# simplefoc.net
KiCad netlist of a schematic drawn in Altium Designer
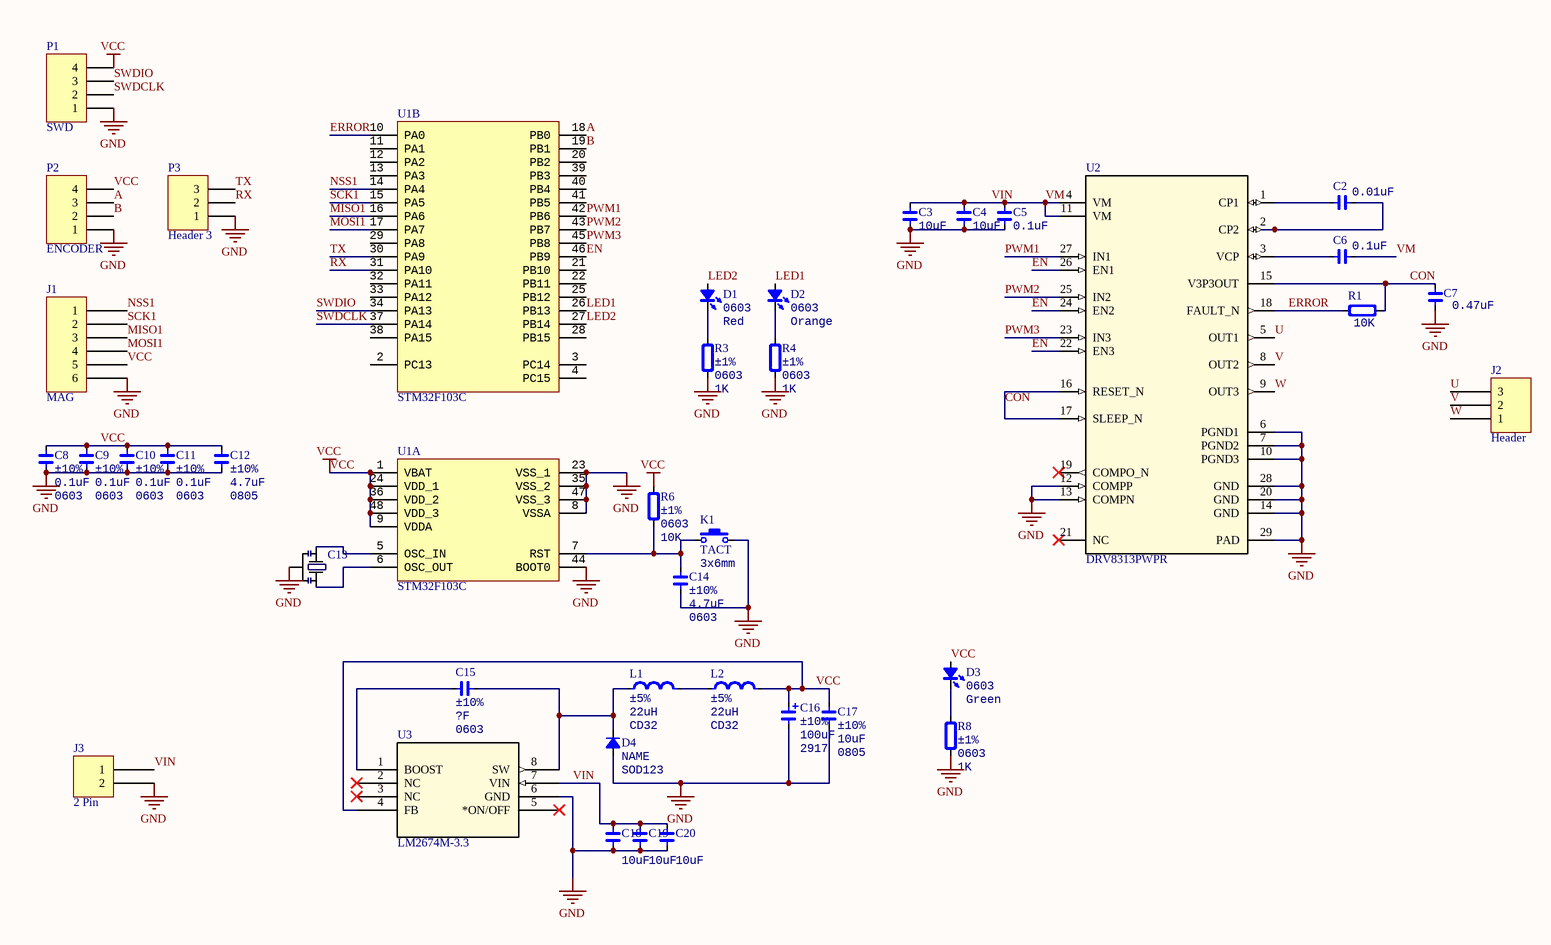
[diagram p0: simplefoc.SchDoc]

(export (version "E")
  (design (tool "Eeschema 10.0.6"))
  (components
    (comp (ref "C2")
      (value "0.01uF")
      (footprint "PCB_PassiveCap:CAP_0603")
      (description "Capacitor")
      (fields (field (name "Comment") "C0603"))
      (libsource (lib "") (part "Cap_0603_1"))
    )
    (comp (ref "C3")
      (value "10uF")
      (footprint "PCB_PassiveCap:CAP_0805")
      (description "Capacitor")
      (fields (field (name "Comment") "C0805"))
      (libsource (lib "SCH_Passive") (part "Cap_0805"))
    )
    (comp (ref "C4")
      (value "10uF")
      (footprint "PCB_PassiveCap:CAP_0805")
      (description "Capacitor")
      (fields (field (name "Comment") "C0805"))
      (libsource (lib "SCH_Passive") (part "Cap_0805"))
    )
    (comp (ref "C5")
      (value "0.1uF")
      (footprint "PCB_PassiveCap:CAP_0603")
      (description "Capacitor")
      (fields (field (name "Comment") "C0603"))
      (libsource (lib "SCH_Passive") (part "Cap_0603"))
    )
    (comp (ref "C6")
      (value "0.1uF")
      (footprint "PCB_PassiveCap:CAP_0603")
      (description "Capacitor")
      (fields (field (name "Comment") "C0603"))
      (libsource (lib "") (part "Cap_0603_1"))
    )
    (comp (ref "C7")
      (value "0.47uF")
      (footprint "PCB_PassiveCap:CAP_0603")
      (description "Capacitor")
      (fields (field (name "Comment") "C0603"))
      (libsource (lib "SCH_Passive") (part "Cap_0603"))
    )
    (comp (ref "C8")
      (value "0.1uF")
      (footprint "PCB_PassiveCap:CAP_0603")
      (description "Capacitor")
      (fields (field (name "NOTE") "±10%") (field (name "TYPE") "0603") (field (name "Comment") "C0603"))
      (libsource (lib "SCH_Passive") (part "Cap_0603"))
    )
    (comp (ref "C9")
      (value "0.1uF")
      (footprint "PCB_PassiveCap:CAP_0603")
      (description "Capacitor")
      (fields (field (name "NOTE") "±10%") (field (name "TYPE") "0603") (field (name "Comment") "C0603"))
      (libsource (lib "SCH_Passive") (part "Cap_0603"))
    )
    (comp (ref "C10")
      (value "0.1uF")
      (footprint "PCB_PassiveCap:CAP_0603")
      (description "Capacitor")
      (fields (field (name "NOTE") "±10%") (field (name "TYPE") "0603") (field (name "Comment") "C0603"))
      (libsource (lib "SCH_Passive") (part "Cap_0603"))
    )
    (comp (ref "C11")
      (value "0.1uF")
      (footprint "PCB_PassiveCap:CAP_0603")
      (description "Capacitor")
      (fields (field (name "NOTE") "±10%") (field (name "TYPE") "0603") (field (name "Comment") "C0603"))
      (libsource (lib "SCH_Passive") (part "Cap_0603"))
    )
    (comp (ref "C12")
      (value "4.7uF")
      (footprint "PCB_PassiveCap:CAP_0805")
      (description "Capacitor")
      (fields (field (name "NOTE") "±10%") (field (name "TYPE") "0805") (field (name "Comment") "C0805"))
      (libsource (lib "SCH_Passive") (part "Cap_0805"))
    )
    (comp (ref "C13")
      (value "CSTCE8M00G52-R0")
      (footprint "CSTCE_MUR")
      (description "No Description Available")
      (fields (field (name "COPYRIGHT") "Copyright (C) 2018 Accelerated Designs. All rights reserved"))
      (libsource (lib "Schlib1") (part "CSTCE8M00G52-R0"))
    )
    (comp (ref "C14")
      (value "4.7uF")
      (footprint "PCB_PassiveCap:CAP_0603")
      (description "Capacitor")
      (fields (field (name "NOTE") "±10%") (field (name "TYPE") "0603") (field (name "Comment") "C0603"))
      (libsource (lib "SCH_Passive") (part "Cap_0603"))
    )
    (comp (ref "C15")
      (value "?F")
      (footprint "PCB_PassiveCap:CAP_0603")
      (description "Capacitor")
      (fields (field (name "NOTE") "±10%") (field (name "TYPE") "0603") (field (name "Comment") "C0603"))
      (libsource (lib "") (part "Cap_0603_1"))
    )
    (comp (ref "C16")
      (value "100uF")
      (footprint "PCB_PassiveCap:CAP_TAN_D2917")
      (description "Capacitor Tantalum")
      (fields (field (name "NOTE") "±10%") (field (name "TYPE") "2917") (field (name "Comment") "C2917"))
      (libsource (lib "SCH_Passive") (part "Cap_Tan_2917"))
    )
    (comp (ref "C17")
      (value "10uF")
      (footprint "PCB_PassiveCap:CAP_0805")
      (description "Capacitor")
      (fields (field (name "NOTE") "±10%") (field (name "TYPE") "0805") (field (name "Comment") "C0805"))
      (libsource (lib "SCH_Passive") (part "Cap_0805"))
    )
    (comp (ref "C18")
      (value "10uF")
      (footprint "PCB_PassiveCap:CAP_0805")
      (description "Capacitor")
      (fields (field (name "Comment") "C0805"))
      (libsource (lib "SCH_Passive") (part "Cap_0805"))
    )
    (comp (ref "C19")
      (value "10uF")
      (footprint "PCB_PassiveCap:CAP_0805")
      (description "Capacitor")
      (fields (field (name "Comment") "C0805"))
      (libsource (lib "SCH_Passive") (part "Cap_0805"))
    )
    (comp (ref "C20")
      (value "10uF")
      (footprint "PCB_PassiveCap:CAP_0805")
      (description "Capacitor")
      (fields (field (name "Comment") "C0805"))
      (libsource (lib "SCH_Passive") (part "Cap_0805"))
    )
    (comp (ref "D1")
      (value "Red")
      (footprint "PCB_ActiveLED:LED_0603_RED")
      (description "LED")
      (fields (field (name "TYPE") "0603") (field (name "Comment") "D0603"))
      (libsource (lib "SCH_Active") (part "LED_0603"))
    )
    (comp (ref "D2")
      (value "Orange")
      (footprint "PCB_ActiveLED:LED_0603_RED")
      (description "LED")
      (fields (field (name "TYPE") "0603") (field (name "Comment") "D0603"))
      (libsource (lib "SCH_Active") (part "LED_0603"))
    )
    (comp (ref "D3")
      (value "Green")
      (footprint "PCB_ActiveLED:LED_0603_RED")
      (description "LED")
      (fields (field (name "TYPE") "0603") (field (name "Comment") "D0603"))
      (libsource (lib "SCH_Active") (part "LED_0603"))
    )
    (comp (ref "D4")
      (value "NAME")
      (footprint "PCB_ActiveDIO:SOD-123")
      (description "Diode")
      (fields (field (name "TYPE") "SOD123"))
      (libsource (lib "SCH_Active") (part "Diode_SOD123"))
    )
    (comp (ref "J1")
      (value "MAG")
      (footprint "JST BM06B-GHS-TBT")
      (libsource (lib "SCH - CONNECTORS - 6 PIN") (part "6 Pin"))
    )
    (comp (ref "J2")
      (value "Header")
      (footprint "Motor_WIRE_3")
      (libsource (lib "SCH - CONNECTORS - 3 PIN") (part "3 Pin"))
    )
    (comp (ref "J3")
      (value "2 Pin")
      (footprint "MOLEX KK 0022272021")
      (libsource (lib "SCH - CONNECTORS - 2 PIN") (part "2 Pin"))
    )
    (comp (ref "K1")
      (value "TACT")
      (footprint "PCB_Switch:ButtonTACT_3x6x2.5_180")
      (description "Button")
      (fields (field (name "ALTIUM_VALUE") "3x6mm"))
      (libsource (lib "SCH_Switch") (part "ButtonTACT_180_3x6x2.5"))
    )
    (comp (ref "L1")
      (value "22uH")
      (footprint "PCB_PassiveInd:IND_CD32")
      (description "Power Inductor")
      (fields (field (name "NOTE") "±5%") (field (name "TYPE") "CD32") (field (name "Comment") "CD32"))
      (libsource (lib "SCH_Passive") (part "Ind_CD32"))
    )
    (comp (ref "L2")
      (value "22uH")
      (footprint "PCB_PassiveInd:IND_CD32")
      (description "Power Inductor")
      (fields (field (name "NOTE") "±5%") (field (name "TYPE") "CD32") (field (name "Comment") "CD32"))
      (libsource (lib "SCH_Passive") (part "Ind_CD32"))
    )
    (comp (ref "P1")
      (value "SWD")
      (footprint "HDR1X4")
      (description "Header, 4-Pin")
      (fields (field (name "PUBLISHER") "Altium Limited"))
      (libsource (lib "Miscellaneous Connectors") (part "Header 4"))
    )
    (comp (ref "P2")
      (value "ENCODER")
      (footprint "HDR1X4")
      (description "Header, 4-Pin")
      (fields (field (name "PUBLISHER") "Altium Limited"))
      (libsource (lib "Miscellaneous Connectors") (part "Header 4"))
    )
    (comp (ref "P3")
      (value "Header 3")
      (footprint "HDR1X3")
      (description "Header, 3-Pin")
      (fields (field (name "PUBLISHER") "Altium Limited"))
      (libsource (lib "Miscellaneous Connectors") (part "Header 3"))
    )
    (comp (ref "R1")
      (value "10K")
      (footprint "PCB_PassiveRes:RES_0603")
      (description "Resistor")
      (fields (field (name "Comment") "R0603"))
      (libsource (lib "SCH_Passive") (part "Res_0603"))
    )
    (comp (ref "R3")
      (value "1K")
      (footprint "PCB_PassiveRes:RES_0603")
      (description "Resistor")
      (fields (field (name "NOTE") "±1%") (field (name "TYPE") "0603") (field (name "Comment") "R0603"))
      (libsource (lib "SCH_Passive") (part "Res_0603"))
    )
    (comp (ref "R4")
      (value "1K")
      (footprint "PCB_PassiveRes:RES_0603")
      (description "Resistor")
      (fields (field (name "NOTE") "±1%") (field (name "TYPE") "0603") (field (name "Comment") "R0603"))
      (libsource (lib "SCH_Passive") (part "Res_0603"))
    )
    (comp (ref "R6")
      (value "10K")
      (footprint "PCB_PassiveRes:RES_0603")
      (description "Resistor")
      (fields (field (name "NOTE") "±1%") (field (name "TYPE") "0603") (field (name "Comment") "R0603"))
      (libsource (lib "SCH_Passive") (part "Res_0603"))
    )
    (comp (ref "R8")
      (value "1K")
      (footprint "PCB_PassiveRes:RES_0603")
      (description "Resistor")
      (fields (field (name "NOTE") "±1%") (field (name "TYPE") "0603") (field (name "Comment") "R0603"))
      (libsource (lib "SCH_Passive") (part "Res_0603"))
    )
    (comp (ref "U1")
      (value "STM32F103C")
      (footprint "PCB_IntegratedCircuit:LQFP_P0.5_48")
      (description "MCU ST")
      (fields (field (name "MANUFACTURER") "STMicroelectronics"))
      (libsource (lib "SCH_Microcontroller") (part "STM32F103C"))
    )
    (comp (ref "U2")
      (value "DRV8313PWPR")
      (footprint "PWP0028F_N")
      (description "No Description Available")
      (fields
        (field (name "MANUFACTURER") "Texas Instruments")
        (field (name "COPYRIGHT") "Copyright (C) 2018 Accelerated Designs. All rights reserved")
      )
      (libsource (lib "Schlib1") (part "DRV8313PWPR"))
    )
    (comp (ref "U3")
      (value "LM2674M-3.3")
      (footprint "M08A_TEX")
      (description "No Description Available")
      (fields (field (name "COPYRIGHT") "Copyright (C) 2018 Accelerated Designs. All rights reserved"))
      (libsource (lib "Schlib1") (part "LM2674M-3.3"))
    )
  )
  (nets
    (net (code "1") (name "/A") (class "Default")
      (node (ref "P2") (pin "3") (pinfunction "3_3") (pintype "passive"))
      (node (ref "U1") (pin "18") (pinfunction "PB0_18") (pintype "passive"))
    )
    (net (code "2") (name "/B") (class "Default")
      (node (ref "P2") (pin "2") (pinfunction "2_2") (pintype "passive"))
      (node (ref "U1") (pin "19") (pinfunction "PB1_19") (pintype "passive"))
    )
    (net (code "3") (name "/CON") (class "Default")
      (node (ref "C7") (pin "2") (pinfunction "2_2") (pintype "passive"))
      (node (ref "R1") (pin "2") (pinfunction "2_2") (pintype "passive"))
      (node (ref "U2") (pin "15") (pinfunction "V3P3OUT_15") (pintype "power_in"))
      (node (ref "U2") (pin "16") (pinfunction "RESET_N_16") (pintype "input"))
      (node (ref "U2") (pin "17") (pinfunction "SLEEP_N_17") (pintype "input"))
    )
    (net (code "4") (name "/EN") (class "Default")
      (node (ref "U1") (pin "46") (pinfunction "PB9_46") (pintype "passive"))
      (node (ref "U2") (pin "22") (pinfunction "EN3_22") (pintype "input"))
      (node (ref "U2") (pin "24") (pinfunction "EN2_24") (pintype "input"))
      (node (ref "U2") (pin "26") (pinfunction "EN1_26") (pintype "input"))
    )
    (net (code "5") (name "/ERROR") (class "Default")
      (node (ref "R1") (pin "1") (pinfunction "1_1") (pintype "passive"))
      (node (ref "U1") (pin "10") (pinfunction "PA0_10") (pintype "passive"))
      (node (ref "U2") (pin "18") (pinfunction "FAULT_N_18") (pintype "output"))
    )
    (net (code "6") (name "/LED1") (class "Default")
      (node (ref "D2") (pin "1") (pinfunction "A_1") (pintype "passive"))
      (node (ref "U1") (pin "26") (pinfunction "PB13_26") (pintype "passive"))
    )
    (net (code "7") (name "/LED2") (class "Default")
      (node (ref "D1") (pin "1") (pinfunction "A_1") (pintype "passive"))
      (node (ref "U1") (pin "27") (pinfunction "PB14_27") (pintype "passive"))
    )
    (net (code "8") (name "/MISO1") (class "Default")
      (node (ref "J1") (pin "3") (pinfunction "3_3") (pintype "passive"))
      (node (ref "U1") (pin "16") (pinfunction "PA6_16") (pintype "passive"))
    )
    (net (code "9") (name "/MOSI1") (class "Default")
      (node (ref "J1") (pin "4") (pinfunction "4_4") (pintype "passive"))
      (node (ref "U1") (pin "17") (pinfunction "PA7_17") (pintype "passive"))
    )
    (net (code "10") (name "/NSS1") (class "Default")
      (node (ref "J1") (pin "1") (pinfunction "1_1") (pintype "passive"))
      (node (ref "U1") (pin "14") (pinfunction "PA4_14") (pintype "passive"))
    )
    (net (code "11") (name "/PWM1") (class "Default")
      (node (ref "U1") (pin "42") (pinfunction "PB6_42") (pintype "passive"))
      (node (ref "U2") (pin "27") (pinfunction "IN1_27") (pintype "input"))
    )
    (net (code "12") (name "/PWM2") (class "Default")
      (node (ref "U1") (pin "43") (pinfunction "PB7_43") (pintype "passive"))
      (node (ref "U2") (pin "25") (pinfunction "IN2_25") (pintype "input"))
    )
    (net (code "13") (name "/PWM3") (class "Default")
      (node (ref "U1") (pin "45") (pinfunction "PB8_45") (pintype "passive"))
      (node (ref "U2") (pin "23") (pinfunction "IN3_23") (pintype "input"))
    )
    (net (code "14") (name "/RX") (class "Default")
      (node (ref "P3") (pin "2") (pinfunction "2_2") (pintype "passive"))
      (node (ref "U1") (pin "31") (pinfunction "PA10_31") (pintype "passive"))
    )
    (net (code "15") (name "/SCK1") (class "Default")
      (node (ref "J1") (pin "2") (pinfunction "2_2") (pintype "passive"))
      (node (ref "U1") (pin "15") (pinfunction "PA5_15") (pintype "passive"))
    )
    (net (code "16") (name "/SWDCLK") (class "Default")
      (node (ref "P1") (pin "2") (pinfunction "2_2") (pintype "passive"))
      (node (ref "U1") (pin "37") (pinfunction "PA14_37") (pintype "passive"))
    )
    (net (code "17") (name "/SWDIO") (class "Default")
      (node (ref "P1") (pin "3") (pinfunction "3_3") (pintype "passive"))
      (node (ref "U1") (pin "34") (pinfunction "PA13_34") (pintype "passive"))
    )
    (net (code "18") (name "/TX") (class "Default")
      (node (ref "P3") (pin "3") (pinfunction "3_3") (pintype "passive"))
      (node (ref "U1") (pin "30") (pinfunction "PA9_30") (pintype "passive"))
    )
    (net (code "19") (name "/U") (class "Default")
      (node (ref "J2") (pin "3") (pinfunction "3_3") (pintype "passive"))
      (node (ref "U2") (pin "5") (pinfunction "OUT1_5") (pintype "output"))
    )
    (net (code "20") (name "/V") (class "Default")
      (node (ref "J2") (pin "2") (pinfunction "2_2") (pintype "passive"))
      (node (ref "U2") (pin "8") (pinfunction "OUT2_8") (pintype "output"))
    )
    (net (code "21") (name "/VIN") (class "Default")
      (node (ref "C18") (pin "2") (pinfunction "2_2") (pintype "passive"))
      (node (ref "C19") (pin "2") (pinfunction "2_2") (pintype "passive"))
      (node (ref "C20") (pin "2") (pinfunction "2_2") (pintype "passive"))
      (node (ref "C3") (pin "2") (pinfunction "2_2") (pintype "passive"))
      (node (ref "C4") (pin "2") (pinfunction "2_2") (pintype "passive"))
      (node (ref "C5") (pin "2") (pinfunction "2_2") (pintype "passive"))
      (node (ref "C6") (pin "2") (pinfunction "2_2") (pintype "passive"))
      (node (ref "J3") (pin "1") (pinfunction "1_1") (pintype "passive"))
      (node (ref "U2") (pin "11") (pinfunction "VM_11") (pintype "power_in"))
      (node (ref "U2") (pin "4") (pinfunction "VM_4") (pintype "power_in"))
      (node (ref "U3") (pin "7") (pinfunction "VIN_7") (pintype "input"))
    )
    (net (code "22") (name "/W") (class "Default")
      (node (ref "J2") (pin "1") (pinfunction "1_1") (pintype "passive"))
      (node (ref "U2") (pin "9") (pinfunction "OUT3_9") (pintype "output"))
    )
    (net (code "23") (name "GND") (class "Default")
      (node (ref "C10") (pin "1") (pinfunction "1_1") (pintype "passive"))
      (node (ref "C11") (pin "1") (pinfunction "1_1") (pintype "passive"))
      (node (ref "C12") (pin "1") (pinfunction "1_1") (pintype "passive"))
      (node (ref "C13") (pin "2") (pinfunction "2_2") (pintype "passive"))
      (node (ref "C14") (pin "1") (pinfunction "1_1") (pintype "passive"))
      (node (ref "C16") (pin "2") (pinfunction "2_2") (pintype "passive"))
      (node (ref "C17") (pin "1") (pinfunction "1_1") (pintype "passive"))
      (node (ref "C18") (pin "1") (pinfunction "1_1") (pintype "passive"))
      (node (ref "C19") (pin "1") (pinfunction "1_1") (pintype "passive"))
      (node (ref "C20") (pin "1") (pinfunction "1_1") (pintype "passive"))
      (node (ref "C3") (pin "1") (pinfunction "1_1") (pintype "passive"))
      (node (ref "C4") (pin "1") (pinfunction "1_1") (pintype "passive"))
      (node (ref "C5") (pin "1") (pinfunction "1_1") (pintype "passive"))
      (node (ref "C7") (pin "1") (pinfunction "1_1") (pintype "passive"))
      (node (ref "C8") (pin "1") (pinfunction "1_1") (pintype "passive"))
      (node (ref "C9") (pin "1") (pinfunction "1_1") (pintype "passive"))
      (node (ref "D4") (pin "1") (pinfunction "A_1") (pintype "passive"))
      (node (ref "J1") (pin "6") (pinfunction "6_6") (pintype "passive"))
      (node (ref "J3") (pin "2") (pinfunction "2_2") (pintype "passive"))
      (node (ref "K1") (pin "1") (pinfunction "1_1") (pintype "passive"))
      (node (ref "P1") (pin "1") (pinfunction "1_1") (pintype "passive"))
      (node (ref "P2") (pin "1") (pinfunction "1_1") (pintype "passive"))
      (node (ref "P3") (pin "1") (pinfunction "1_1") (pintype "passive"))
      (node (ref "R3") (pin "1") (pinfunction "1_1") (pintype "passive"))
      (node (ref "R4") (pin "1") (pinfunction "1_1") (pintype "passive"))
      (node (ref "R8") (pin "1") (pinfunction "1_1") (pintype "passive"))
      (node (ref "U1") (pin "23") (pinfunction "VSS_1_23") (pintype "passive"))
      (node (ref "U1") (pin "35") (pinfunction "VSS_2_35") (pintype "passive"))
      (node (ref "U1") (pin "44") (pinfunction "BOOT0_44") (pintype "passive"))
      (node (ref "U1") (pin "47") (pinfunction "VSS_3_47") (pintype "passive"))
      (node (ref "U1") (pin "8") (pinfunction "VSSA_8") (pintype "passive"))
      (node (ref "U2") (pin "10") (pinfunction "PGND3_10") (pintype "power_in"))
      (node (ref "U2") (pin "12") (pinfunction "COMPP_12") (pintype "input"))
      (node (ref "U2") (pin "13") (pinfunction "COMPN_13") (pintype "input"))
      (node (ref "U2") (pin "14") (pinfunction "GND_14") (pintype "power_in"))
      (node (ref "U2") (pin "20") (pinfunction "GND_20") (pintype "power_in"))
      (node (ref "U2") (pin "28") (pinfunction "GND_28") (pintype "power_in"))
      (node (ref "U2") (pin "29") (pinfunction "PAD_29") (pintype "power_in"))
      (node (ref "U2") (pin "6") (pinfunction "PGND1_6") (pintype "power_in"))
      (node (ref "U2") (pin "7") (pinfunction "PGND2_7") (pintype "power_in"))
      (node (ref "U3") (pin "6") (pinfunction "GND_6") (pintype "passive"))
    )
    (net (code "24") (name "Net-(D1-K)") (class "Default")
      (node (ref "D1") (pin "2") (pinfunction "K_2") (pintype "passive"))
      (node (ref "R3") (pin "2") (pinfunction "2_2") (pintype "passive"))
    )
    (net (code "25") (name "Net-(D2-K)") (class "Default")
      (node (ref "D2") (pin "2") (pinfunction "K_2") (pintype "passive"))
      (node (ref "R4") (pin "2") (pinfunction "2_2") (pintype "passive"))
    )
    (net (code "26") (name "Net-(D3-K)") (class "Default")
      (node (ref "D3") (pin "2") (pinfunction "K_2") (pintype "passive"))
      (node (ref "R8") (pin "2") (pinfunction "2_2") (pintype "passive"))
    )
    (net (code "27") (name "Net-(D4-K)") (class "Default")
      (node (ref "C15") (pin "2") (pinfunction "2_2") (pintype "passive"))
      (node (ref "D4") (pin "2") (pinfunction "K_2") (pintype "passive"))
      (node (ref "L1") (pin "1") (pinfunction "1_1") (pintype "passive"))
      (node (ref "U3") (pin "8") (pinfunction "SW_8") (pintype "output"))
    )
    (net (code "28") (name "Net-(L1-Pad2)") (class "Default")
      (node (ref "L1") (pin "2") (pinfunction "2_2") (pintype "passive"))
      (node (ref "L2") (pin "1") (pinfunction "1_1") (pintype "passive"))
    )
    (net (code "29") (name "Net-(U1A-OSC_IN)") (class "Default")
      (node (ref "C13") (pin "1") (pinfunction "1_1") (pintype "passive"))
      (node (ref "U1") (pin "5") (pinfunction "OSC_IN_5") (pintype "passive"))
    )
    (net (code "30") (name "Net-(U1A-OSC_OUT)") (class "Default")
      (node (ref "C13") (pin "3") (pinfunction "3_3") (pintype "passive"))
      (node (ref "U1") (pin "6") (pinfunction "OSC_OUT_6") (pintype "passive"))
    )
    (net (code "31") (name "Net-(U1A-RST)") (class "Default")
      (node (ref "C14") (pin "2") (pinfunction "2_2") (pintype "passive"))
      (node (ref "K1") (pin "2") (pinfunction "2_2") (pintype "passive"))
      (node (ref "R6") (pin "1") (pinfunction "1_1") (pintype "passive"))
      (node (ref "U1") (pin "7") (pinfunction "RST_7") (pintype "passive"))
    )
    (net (code "32") (name "Net-(U2-CP1)") (class "Default")
      (node (ref "C2") (pin "1") (pinfunction "1_1") (pintype "passive"))
      (node (ref "U2") (pin "1") (pinfunction "CP1_1") (pintype "bidirectional"))
    )
    (net (code "33") (name "Net-(U2-CP2)") (class "Default")
      (node (ref "C2") (pin "2") (pinfunction "2_2") (pintype "passive"))
      (node (ref "U2") (pin "2") (pinfunction "CP2_2") (pintype "bidirectional"))
    )
    (net (code "34") (name "Net-(U2-VCP)") (class "Default")
      (node (ref "C6") (pin "1") (pinfunction "1_1") (pintype "passive"))
      (node (ref "U2") (pin "3") (pinfunction "VCP_3") (pintype "bidirectional"))
    )
    (net (code "35") (name "Net-(U3-BOOST)") (class "Default")
      (node (ref "C15") (pin "1") (pinfunction "1_1") (pintype "passive"))
      (node (ref "U3") (pin "1") (pinfunction "BOOST_1") (pintype "passive"))
    )
    (net (code "36") (name "VCC") (class "Default")
      (node (ref "C10") (pin "2") (pinfunction "2_2") (pintype "passive"))
      (node (ref "C11") (pin "2") (pinfunction "2_2") (pintype "passive"))
      (node (ref "C12") (pin "2") (pinfunction "2_2") (pintype "passive"))
      (node (ref "C16") (pin "1") (pinfunction "1_1") (pintype "passive"))
      (node (ref "C17") (pin "2") (pinfunction "2_2") (pintype "passive"))
      (node (ref "C8") (pin "2") (pinfunction "2_2") (pintype "passive"))
      (node (ref "C9") (pin "2") (pinfunction "2_2") (pintype "passive"))
      (node (ref "D3") (pin "1") (pinfunction "A_1") (pintype "passive"))
      (node (ref "J1") (pin "5") (pinfunction "5_5") (pintype "passive"))
      (node (ref "L2") (pin "2") (pinfunction "2_2") (pintype "passive"))
      (node (ref "P1") (pin "4") (pinfunction "4_4") (pintype "passive"))
      (node (ref "P2") (pin "4") (pinfunction "4_4") (pintype "passive"))
      (node (ref "R6") (pin "2") (pinfunction "2_2") (pintype "passive"))
      (node (ref "U1") (pin "1") (pinfunction "VBAT_1") (pintype "passive"))
      (node (ref "U1") (pin "24") (pinfunction "VDD_1_24") (pintype "passive"))
      (node (ref "U1") (pin "36") (pinfunction "VDD_2_36") (pintype "passive"))
      (node (ref "U1") (pin "48") (pinfunction "VDD_3_48") (pintype "passive"))
      (node (ref "U1") (pin "9") (pinfunction "VDDA_9") (pintype "passive"))
      (node (ref "U3") (pin "4") (pinfunction "FB_4") (pintype "passive"))
    )
    (net (code "37") (name "unconnected-(U1B-PA1-Pad11)") (class "Default")
      (node (ref "U1") (pin "11") (pinfunction "PA1_11") (pintype "passive"))
    )
    (net (code "38") (name "unconnected-(U1B-PA2-Pad12)") (class "Default")
      (node (ref "U1") (pin "12") (pinfunction "PA2_12") (pintype "passive"))
    )
    (net (code "39") (name "unconnected-(U1B-PA3-Pad13)") (class "Default")
      (node (ref "U1") (pin "13") (pinfunction "PA3_13") (pintype "passive"))
    )
    (net (code "40") (name "unconnected-(U1B-PA8-Pad29)") (class "Default")
      (node (ref "U1") (pin "29") (pinfunction "PA8_29") (pintype "passive"))
    )
    (net (code "41") (name "unconnected-(U1B-PA11-Pad32)") (class "Default")
      (node (ref "U1") (pin "32") (pinfunction "PA11_32") (pintype "passive"))
    )
    (net (code "42") (name "unconnected-(U1B-PA12-Pad33)") (class "Default")
      (node (ref "U1") (pin "33") (pinfunction "PA12_33") (pintype "passive"))
    )
    (net (code "43") (name "unconnected-(U1B-PA15-Pad38)") (class "Default")
      (node (ref "U1") (pin "38") (pinfunction "PA15_38") (pintype "passive"))
    )
    (net (code "44") (name "unconnected-(U1B-PB2-Pad20)") (class "Default")
      (node (ref "U1") (pin "20") (pinfunction "PB2_20") (pintype "passive"))
    )
    (net (code "45") (name "unconnected-(U1B-PB3-Pad39)") (class "Default")
      (node (ref "U1") (pin "39") (pinfunction "PB3_39") (pintype "passive"))
    )
    (net (code "46") (name "unconnected-(U1B-PB4-Pad40)") (class "Default")
      (node (ref "U1") (pin "40") (pinfunction "PB4_40") (pintype "passive"))
    )
    (net (code "47") (name "unconnected-(U1B-PB5-Pad41)") (class "Default")
      (node (ref "U1") (pin "41") (pinfunction "PB5_41") (pintype "passive"))
    )
    (net (code "48") (name "unconnected-(U1B-PB10-Pad21)") (class "Default")
      (node (ref "U1") (pin "21") (pinfunction "PB10_21") (pintype "passive"))
    )
    (net (code "49") (name "unconnected-(U1B-PB11-Pad22)") (class "Default")
      (node (ref "U1") (pin "22") (pinfunction "PB11_22") (pintype "passive"))
    )
    (net (code "50") (name "unconnected-(U1B-PB12-Pad25)") (class "Default")
      (node (ref "U1") (pin "25") (pinfunction "PB12_25") (pintype "passive"))
    )
    (net (code "51") (name "unconnected-(U1B-PB15-Pad28)") (class "Default")
      (node (ref "U1") (pin "28") (pinfunction "PB15_28") (pintype "passive"))
    )
    (net (code "52") (name "unconnected-(U1B-PC13-Pad2)") (class "Default")
      (node (ref "U1") (pin "2") (pinfunction "PC13_2") (pintype "passive"))
    )
    (net (code "53") (name "unconnected-(U1B-PC14-Pad3)") (class "Default")
      (node (ref "U1") (pin "3") (pinfunction "PC14_3") (pintype "passive"))
    )
    (net (code "54") (name "unconnected-(U1B-PC15-Pad4)") (class "Default")
      (node (ref "U1") (pin "4") (pinfunction "PC15_4") (pintype "passive"))
    )
    (net (code "55") (name "unconnected-(U2-COMPO_N-Pad19)") (class "Default")
      (node (ref "U2") (pin "19") (pinfunction "COMPO_N_19") (pintype "output+no_connect"))
    )
    (net (code "56") (name "unconnected-(U2-NC-Pad21)") (class "Default")
      (node (ref "U2") (pin "21") (pinfunction "NC_21") (pintype "passive+no_connect"))
    )
    (net (code "57") (name "unconnected-(U3-*ON{slash}OFF-Pad5)") (class "Default")
      (node (ref "U3") (pin "5") (pinfunction "*ON/OFF_5") (pintype "passive+no_connect"))
    )
    (net (code "58") (name "unconnected-(U3-NC-Pad2)") (class "Default")
      (node (ref "U3") (pin "2") (pinfunction "NC_2") (pintype "passive+no_connect"))
    )
    (net (code "59") (name "unconnected-(U3-NC-Pad3)") (class "Default")
      (node (ref "U3") (pin "3") (pinfunction "NC_3") (pintype "passive+no_connect"))
    )
  )
)
